# RS-485_Transceiver.net
KiCad netlist of a schematic drawn in Altium Designer
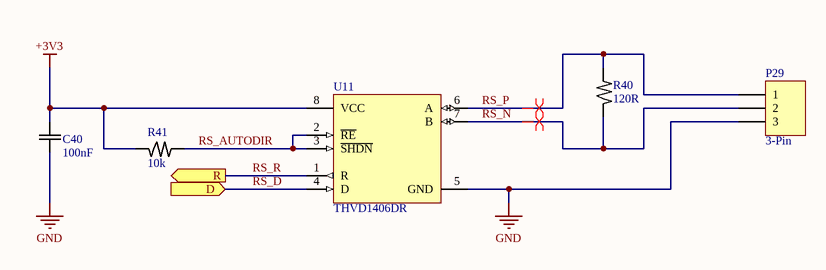
[diagram p0: RS-485 Transceiver.SchDoc]

(export (version "E")
  (design (tool "Eeschema 10.0.6"))
  (components
    (comp (ref "C40")
      (value "100nF")
      (footprint "C0603")
      (description "CAP CER 100nF 50V X7R 0603")
      (fields (field (name "MF") "HRE") (field (name "MP") "CGA0603X7R104K500JT"))
      (libsource (lib "Components") (part "Cap_cer"))
    )
    (comp (ref "P29")
      (value "3-Pin")
      (footprint "Spring Terminal Block 3-Pin")
      (description "3 Position Wire to Board Terminal Block 2.54mm Through Hole, Right Angle")
      (fields (field (name "MF") "DORABO") (field (name "MP") "DB141R-2.54-3P-GN"))
      (libsource (lib "Connectors") (part "Spring Terminal 3-Pin"))
    )
    (comp (ref "R40")
      (value "120R")
      (footprint "R0603")
      (description "RES 120Ω ±1% 100mW 0603")
      (fields (field (name "MF") "UNI-ROYAL") (field (name "MP") "0603WAF1200T5E"))
      (libsource (lib "Components") (part "Res"))
    )
    (comp (ref "R41")
      (value "10k")
      (footprint "R0603")
      (description "RES 10kΩ ±1% 100mW 0603")
      (fields (field (name "MF") "FOJAN") (field (name "MP") "FRC0603F1002TS"))
      (libsource (lib "Components") (part "Res"))
    )
    (comp (ref "U11")
      (value "THVD1406DR")
      (footprint "SOIC-8")
      (description "1/1 Transceiver Half RS422, RS485 SOIC-8")
      (fields (field (name "MF") "Texas Instruments"))
      (libsource (lib "Components") (part "THVD1406DR RS-485"))
    )
  )
  (nets
    (net (code "1") (name "+3V3") (class "Default")
      (node (ref "C40") (pin "2") (pinfunction "2_2") (pintype "passive"))
      (node (ref "R41") (pin "2") (pinfunction "2_2") (pintype "passive"))
      (node (ref "U11") (pin "8") (pinfunction "VCC_8") (pintype "power_in"))
    )
    (net (code "2") (name "/RS_AUTODIR") (class "Default")
      (node (ref "R41") (pin "1") (pinfunction "1_1") (pintype "passive"))
      (node (ref "U11") (pin "2") (pinfunction "~{RE}_2") (pintype "input"))
      (node (ref "U11") (pin "3") (pinfunction "~{SHDN}_3") (pintype "input"))
    )
    (net (code "3") (name "/RS_D") (class "Default")
      (node (ref "U11") (pin "4") (pinfunction "D_4") (pintype "input"))
    )
    (net (code "4") (name "/RS_N") (class "Default")
      (node (ref "P29") (pin "2") (pinfunction "2_2") (pintype "passive"))
      (node (ref "R40") (pin "2") (pinfunction "2_2") (pintype "passive"))
      (node (ref "U11") (pin "7") (pinfunction "B_7") (pintype "bidirectional"))
    )
    (net (code "5") (name "/RS_P") (class "Default")
      (node (ref "P29") (pin "1") (pinfunction "1_1") (pintype "passive"))
      (node (ref "R40") (pin "1") (pinfunction "1_1") (pintype "passive"))
      (node (ref "U11") (pin "6") (pinfunction "A_6") (pintype "bidirectional"))
    )
    (net (code "6") (name "/RS_R") (class "Default")
      (node (ref "U11") (pin "1") (pinfunction "R_1") (pintype "output"))
    )
    (net (code "7") (name "GND") (class "Default")
      (node (ref "C40") (pin "1") (pinfunction "1_1") (pintype "passive"))
      (node (ref "P29") (pin "3") (pinfunction "3_3") (pintype "passive"))
      (node (ref "U11") (pin "5") (pinfunction "GND_5") (pintype "power_in"))
    )
  )
)
